# V1_0.net
KiCad netlist of a schematic drawn in Altium Designer
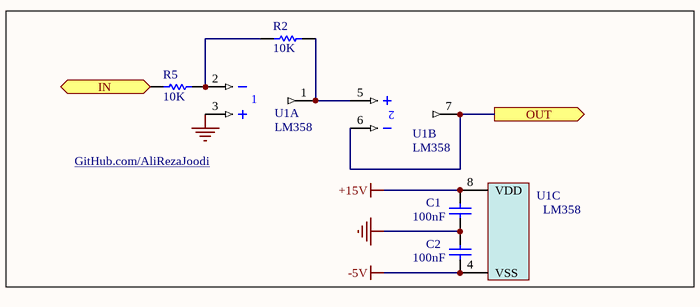
[diagram p0: V1.0.SchDoc]

(export (version "E")
  (design (tool "Eeschema 10.0.6"))
  (components
    (comp (ref "C1")
      (value "100nF")
      (footprint "CAPNTO2.54-3.05x1.78A")
      (description "Capacitor")
      (fields
        (field (name "MANUFACTURER") "Generic Components")
        (field (name "Comment") "Cap")
        (field (name "PUBLISHER") "Altium Limited")
      )
      (libsource (lib "Miscellaneous Devices") (part "Cap"))
    )
    (comp (ref "C2")
      (value "100nF")
      (footprint "CAPNTO2.54-3.05x1.78A")
      (description "Capacitor")
      (fields
        (field (name "MANUFACTURER") "Generic Components")
        (field (name "Comment") "Cap")
        (field (name "PUBLISHER") "Altium Limited")
      )
      (libsource (lib "Miscellaneous Devices") (part "Cap"))
    )
    (comp (ref "R2")
      (value "10K")
      (footprint "AXIAL-0.4")
      (description "Resistor")
      (fields (field (name "PUBLISHER") "Altium Limited"))
      (libsource (lib "Miscellaneous Devices") (part "Res1"))
    )
    (comp (ref "R5")
      (value "10K")
      (footprint "AXIAL-0.4")
      (description "Resistor")
      (fields (field (name "PUBLISHER") "Altium Limited"))
      (libsource (lib "Miscellaneous Devices") (part "Res1"))
    )
    (comp (ref "U1")
      (value "LM358")
      (footprint "751-02_L")
      (description "Dual Low-Power Operational Amplifier")
      (fields (field (name "PUBLISHER") "Altium Limited"))
      (libsource (lib "my Libraries") (part "LM358"))
    )
  )
  (nets
    (net (code "1") (name "+15V") (class "Default")
      (node (ref "C1") (pin "1") (pinfunction "1_1") (pintype "passive"))
      (node (ref "U1") (pin "8") (pinfunction "VDD_8") (pintype "passive"))
    )
    (net (code "2") (name "-5V") (class "Default")
      (node (ref "C2") (pin "2") (pinfunction "2_2") (pintype "passive"))
      (node (ref "U1") (pin "4") (pinfunction "VSS_4") (pintype "power_in"))
    )
    (net (code "3") (name "/IN") (class "Default")
      (node (ref "R5") (pin "2") (pinfunction "2_2") (pintype "passive"))
    )
    (net (code "4") (name "/OUT") (class "Default")
      (node (ref "U1") (pin "6") (pinfunction "IN-_6") (pintype "input"))
      (node (ref "U1") (pin "7") (pinfunction "OUT_7") (pintype "output"))
    )
    (net (code "5") (name "GND") (class "Default")
      (node (ref "C1") (pin "2") (pinfunction "2_2") (pintype "passive"))
      (node (ref "C2") (pin "1") (pinfunction "1_1") (pintype "passive"))
      (node (ref "U1") (pin "3") (pinfunction "IN+_3") (pintype "input"))
    )
    (net (code "6") (name "Net-(U1A-IN-)") (class "Default")
      (node (ref "R2") (pin "1") (pinfunction "1_1") (pintype "passive"))
      (node (ref "R5") (pin "1") (pinfunction "1_1") (pintype "passive"))
      (node (ref "U1") (pin "2") (pinfunction "IN-_2") (pintype "input"))
    )
    (net (code "7") (name "Net-(U1A-OUT)") (class "Default")
      (node (ref "R2") (pin "2") (pinfunction "2_2") (pintype "passive"))
      (node (ref "U1") (pin "1") (pinfunction "OUT_1") (pintype "output"))
      (node (ref "U1") (pin "5") (pinfunction "IN+_5") (pintype "input"))
    )
  )
)
